# SL_LCD_SW_LED_2E.net
KiCad netlist of a schematic drawn in Altium Designer
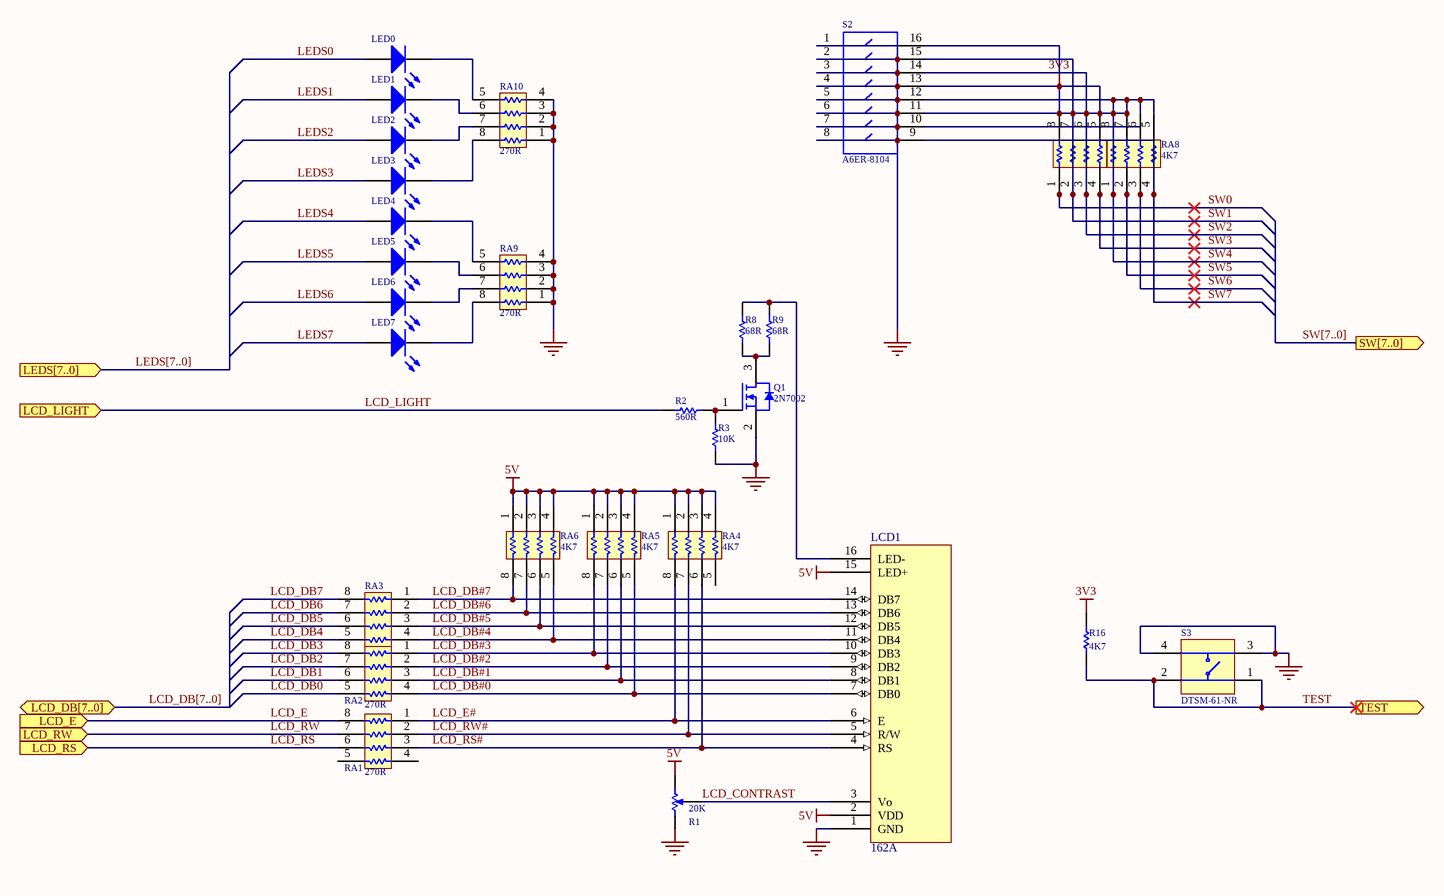
[diagram p0: SL_LCD_SW_LED_2E.SchDoc]

(export (version "E")
  (design (tool "Eeschema 10.0.6"))
  (components
    (comp (ref "LCD1")
      (value "162A")
      (footprint "Spirit_Level_Project:162A")
      (description "16 char * 2 line LCD character display with b/light")
      (libsource (lib "SpiritLevel_2E") (part "162A"))
    )
    (comp (ref "LED0")
      (value "HSMH-C170")
      (footprint "Spirit_Level_Project:SMD _LED")
      (description "Typical RED GaAs SMD LED Agilent make")
      (libsource (lib "SpiritLevel_2E") (part "HSMX-C670"))
    )
    (comp (ref "LED1")
      (value "HSMH-C170")
      (footprint "Spirit_Level_Project:SMD _LED")
      (description "Typical RED GaAs SMD LED Agilent make")
      (libsource (lib "SpiritLevel_2E") (part "HSMX-C670"))
    )
    (comp (ref "LED2")
      (value "HSMH-C170")
      (footprint "Spirit_Level_Project:SMD _LED")
      (description "Typical RED GaAs SMD LED Agilent make")
      (libsource (lib "SpiritLevel_2E") (part "HSMX-C670"))
    )
    (comp (ref "LED3")
      (value "HSMH-C170")
      (footprint "Spirit_Level_Project:SMD _LED")
      (description "Typical RED GaAs SMD LED Agilent make")
      (libsource (lib "SpiritLevel_2E") (part "HSMX-C670"))
    )
    (comp (ref "LED4")
      (value "HSMH-C170")
      (footprint "Spirit_Level_Project:SMD _LED")
      (description "Typical RED GaAs SMD LED Agilent make")
      (libsource (lib "SpiritLevel_2E") (part "HSMX-C670"))
    )
    (comp (ref "LED5")
      (value "HSMH-C170")
      (footprint "Spirit_Level_Project:SMD _LED")
      (description "Typical RED GaAs SMD LED Agilent make")
      (libsource (lib "SpiritLevel_2E") (part "HSMX-C670"))
    )
    (comp (ref "LED6")
      (value "HSMH-C170")
      (footprint "Spirit_Level_Project:SMD _LED")
      (description "Typical RED GaAs SMD LED Agilent make")
      (libsource (lib "SpiritLevel_2E") (part "HSMX-C670"))
    )
    (comp (ref "LED7")
      (value "HSMH-C170")
      (footprint "Spirit_Level_Project:SMD _LED")
      (description "Typical RED GaAs SMD LED Agilent make")
      (libsource (lib "SpiritLevel_2E") (part "HSMX-C670"))
    )
    (comp (ref "Q1")
      (value "2N7002")
      (footprint "Spirit_Level_Project:SO-G3")
      (description "N Channel Mosfet")
      (libsource (lib "SpiritLevel_2E") (part "2N7002"))
    )
    (comp (ref "R1")
      (value "20K")
      (footprint "Spirit_Level_Project:POT4MM-2")
      (description "Square Trimming Potentiometer")
      (libsource (lib "SpiritLevel_2E") (part "RPot SM"))
    )
    (comp (ref "R2")
      (value "560R")
      (footprint "CC2012-0805")
      (description "Resistor")
      (libsource (lib "SpiritLevel_2E") (part "RES"))
    )
    (comp (ref "R3")
      (value "10K")
      (footprint "CC2012-0805")
      (description "Resistor")
      (libsource (lib "SpiritLevel_2E") (part "RES"))
    )
    (comp (ref "R8")
      (value "68R")
      (footprint "CC2012-0805")
      (description "Resistor")
      (libsource (lib "") (part "RES_1"))
    )
    (comp (ref "R9")
      (value "68R")
      (footprint "CC2012-0805")
      (description "Resistor")
      (libsource (lib "") (part "RES_1"))
    )
    (comp (ref "R16")
      (value "4K7")
      (footprint "CC2012-0805")
      (description "Resistor")
      (libsource (lib "SpiritLevel_2E") (part "RES"))
    )
    (comp (ref "RA1")
      (value "270R")
      (footprint "Spirit_Level_Project:MNR34")
      (description "3216x4 Resistor Array")
      (libsource (lib "SpiritLevel_2E") (part "MNR34"))
    )
    (comp (ref "RA2")
      (value "270R")
      (footprint "Spirit_Level_Project:MNR34")
      (description "3216x4 Resistor Array")
      (libsource (lib "SpiritLevel_2E") (part "MNR34"))
    )
    (comp (ref "RA3")
      (value "270R")
      (footprint "Spirit_Level_Project:MNR34")
      (description "3216x4 Resistor Array")
      (libsource (lib "SpiritLevel_2E") (part "MNR34"))
    )
    (comp (ref "RA4")
      (value "4K7")
      (footprint "Spirit_Level_Project:MNR34T")
      (description "3216x4 Resistor Array")
      (libsource (lib "") (part "MNR34_1"))
    )
    (comp (ref "RA5")
      (value "4K7")
      (footprint "Spirit_Level_Project:MNR34T")
      (description "3216x4 Resistor Array")
      (libsource (lib "") (part "MNR34_1"))
    )
    (comp (ref "RA6")
      (value "4K7")
      (footprint "Spirit_Level_Project:MNR34T")
      (description "3216x4 Resistor Array")
      (libsource (lib "") (part "MNR34_1"))
    )
    (comp (ref "RA7")
      (value "4K7")
      (footprint "Spirit_Level_Project:MNR34T")
      (description "3216x4 Resistor Array")
      (libsource (lib "") (part "MNR34_3"))
    )
    (comp (ref "RA8")
      (value "4K7")
      (footprint "Spirit_Level_Project:MNR34T")
      (description "3216x4 Resistor Array")
      (libsource (lib "") (part "MNR34_3"))
    )
    (comp (ref "RA9")
      (value "270R")
      (footprint "Spirit_Level_Project:MNR34T")
      (description "3216x4 Resistor Array")
      (libsource (lib "") (part "MNR34_2"))
    )
    (comp (ref "RA10")
      (value "270R")
      (footprint "Spirit_Level_Project:MNR34T")
      (description "3216x4 Resistor Array")
      (libsource (lib "") (part "MNR34_2"))
    )
    (comp (ref "S2")
      (value "A6ER-8104")
      (footprint "Spirit_Level_Project:DIP-16-KEY")
      (description "DIP Switch Side actuator long liver Piano Key")
      (libsource (lib "SpiritLevel_2E") (part "A6ER-8104"))
    )
    (comp (ref "S3")
      (value "DTSM-61-NR")
      (footprint "Spirit_Level_Project:B3FS_SWITCH")
      (description "SPNA SMD Keyboard Switch")
      (libsource (lib "SpiritLevel_2E") (part "B3FS"))
    )
  )
  (nets
    (net (code "1") (name "/LCD_CONTRAST") (class "Default")
      (node (ref "LCD1") (pin "3") (pinfunction "Vo_3") (pintype "tri_state"))
      (node (ref "R1") (pin "W") (pintype "passive"))
    )
    (net (code "2") (name "/LCD_DB#0") (class "Default")
      (node (ref "LCD1") (pin "7") (pinfunction "DB0_7") (pintype "bidirectional"))
      (node (ref "RA2") (pin "4") (pintype "passive"))
      (node (ref "RA5") (pin "5") (pintype "passive"))
    )
    (net (code "3") (name "/LCD_DB#1") (class "Default")
      (node (ref "LCD1") (pin "8") (pinfunction "DB1_8") (pintype "bidirectional"))
      (node (ref "RA2") (pin "3") (pintype "passive"))
      (node (ref "RA5") (pin "6") (pintype "passive"))
    )
    (net (code "4") (name "/LCD_DB#2") (class "Default")
      (node (ref "LCD1") (pin "9") (pinfunction "DB2_9") (pintype "bidirectional"))
      (node (ref "RA2") (pin "2") (pintype "passive"))
      (node (ref "RA5") (pin "7") (pintype "passive"))
    )
    (net (code "5") (name "/LCD_DB#3") (class "Default")
      (node (ref "LCD1") (pin "10") (pinfunction "DB3_10") (pintype "bidirectional"))
      (node (ref "RA2") (pin "1") (pintype "passive"))
      (node (ref "RA5") (pin "8") (pintype "passive"))
    )
    (net (code "6") (name "/LCD_DB#4") (class "Default")
      (node (ref "LCD1") (pin "11") (pinfunction "DB4_11") (pintype "bidirectional"))
      (node (ref "RA3") (pin "4") (pintype "passive"))
      (node (ref "RA6") (pin "5") (pintype "passive"))
    )
    (net (code "7") (name "/LCD_DB#5") (class "Default")
      (node (ref "LCD1") (pin "12") (pinfunction "DB5_12") (pintype "bidirectional"))
      (node (ref "RA3") (pin "3") (pintype "passive"))
      (node (ref "RA6") (pin "6") (pintype "passive"))
    )
    (net (code "8") (name "/LCD_DB#6") (class "Default")
      (node (ref "LCD1") (pin "13") (pinfunction "DB6_13") (pintype "bidirectional"))
      (node (ref "RA3") (pin "2") (pintype "passive"))
      (node (ref "RA6") (pin "7") (pintype "passive"))
    )
    (net (code "9") (name "/LCD_DB#7") (class "Default")
      (node (ref "LCD1") (pin "14") (pinfunction "DB7_14") (pintype "bidirectional"))
      (node (ref "RA3") (pin "1") (pintype "passive"))
      (node (ref "RA6") (pin "8") (pintype "passive"))
    )
    (net (code "10") (name "/LCD_DB0") (class "Default") (node (ref "RA2") (pin "5") (pintype "passive")))
    (net (code "11") (name "/LCD_DB1") (class "Default") (node (ref "RA2") (pin "6") (pintype "passive")))
    (net (code "12") (name "/LCD_DB2") (class "Default") (node (ref "RA2") (pin "7") (pintype "passive")))
    (net (code "13") (name "/LCD_DB3") (class "Default") (node (ref "RA2") (pin "8") (pintype "passive")))
    (net (code "14") (name "/LCD_DB4") (class "Default") (node (ref "RA3") (pin "5") (pintype "passive")))
    (net (code "15") (name "/LCD_DB5") (class "Default") (node (ref "RA3") (pin "6") (pintype "passive")))
    (net (code "16") (name "/LCD_DB6") (class "Default") (node (ref "RA3") (pin "7") (pintype "passive")))
    (net (code "17") (name "/LCD_DB7") (class "Default") (node (ref "RA3") (pin "8") (pintype "passive")))
    (net (code "19") (name "/LCD_E") (class "Default") (node (ref "RA1") (pin "8") (pintype "passive")))
    (net (code "20") (name "/LCD_E#") (class "Default")
      (node (ref "LCD1") (pin "6") (pinfunction "E_6") (pintype "input"))
      (node (ref "RA1") (pin "1") (pintype "passive"))
      (node (ref "RA4") (pin "8") (pintype "passive"))
    )
    (net (code "21") (name "/LCD_LIGHT") (class "Default")
      (node (ref "R2") (pin "1") (pinfunction "1_1") (pintype "passive"))
    )
    (net (code "22") (name "/LCD_RS") (class "Default") (node (ref "RA1") (pin "6") (pintype "passive")))
    (net (code "23") (name "/LCD_RS#") (class "Default")
      (node (ref "LCD1") (pin "4") (pinfunction "RS_4") (pintype "input"))
      (node (ref "RA1") (pin "3") (pintype "passive"))
      (node (ref "RA4") (pin "6") (pintype "passive"))
    )
    (net (code "24") (name "/LCD_RW") (class "Default") (node (ref "RA1") (pin "7") (pintype "passive")))
    (net (code "25") (name "/LCD_RW#") (class "Default")
      (node (ref "LCD1") (pin "5") (pinfunction "R/W_5") (pintype "input"))
      (node (ref "RA1") (pin "2") (pintype "passive"))
      (node (ref "RA4") (pin "7") (pintype "passive"))
    )
    (net (code "26") (name "/LEDS0") (class "Default")
      (node (ref "LED0") (pin "1") (pinfunction "A_1") (pintype "passive"))
    )
    (net (code "27") (name "/LEDS1") (class "Default")
      (node (ref "LED1") (pin "1") (pinfunction "A_1") (pintype "passive"))
    )
    (net (code "28") (name "/LEDS2") (class "Default")
      (node (ref "LED2") (pin "1") (pinfunction "A_1") (pintype "passive"))
    )
    (net (code "29") (name "/LEDS3") (class "Default")
      (node (ref "LED3") (pin "1") (pinfunction "A_1") (pintype "passive"))
    )
    (net (code "30") (name "/LEDS4") (class "Default")
      (node (ref "LED4") (pin "1") (pinfunction "A_1") (pintype "passive"))
    )
    (net (code "31") (name "/LEDS5") (class "Default")
      (node (ref "LED5") (pin "1") (pinfunction "A_1") (pintype "passive"))
    )
    (net (code "32") (name "/LEDS6") (class "Default")
      (node (ref "LED6") (pin "1") (pinfunction "A_1") (pintype "passive"))
    )
    (net (code "33") (name "/LEDS7") (class "Default")
      (node (ref "LED7") (pin "1") (pinfunction "A_1") (pintype "passive"))
    )
    (net (code "35") (name "/SW6") (class "Default")
      (node (ref "RA8") (pin "3") (pintype "passive"))
      (node (ref "S2") (pin "10") (pinfunction "10_10") (pintype "passive"))
    )
    (net (code "36") (name "/SW7") (class "Default")
      (node (ref "RA8") (pin "4") (pintype "passive"))
      (node (ref "S2") (pin "9") (pinfunction "9_9") (pintype "passive"))
    )
    (net (code "38") (name "/TEST") (class "Default")
      (node (ref "R16") (pin "2") (pinfunction "2_2") (pintype "passive"))
      (node (ref "S3") (pin "1") (pinfunction "1_1") (pintype "passive"))
      (node (ref "S3") (pin "2") (pinfunction "2_2") (pintype "passive"))
    )
    (net (code "39") (name "3V3") (class "Default")
      (node (ref "R16") (pin "1") (pinfunction "1_1") (pintype "passive"))
      (node (ref "RA7") (pin "1") (pintype "passive"))
      (node (ref "RA7") (pin "2") (pintype "passive"))
      (node (ref "RA7") (pin "3") (pintype "passive"))
      (node (ref "RA7") (pin "4") (pintype "passive"))
      (node (ref "RA7") (pin "5") (pintype "passive"))
      (node (ref "RA7") (pin "6") (pintype "passive"))
      (node (ref "RA7") (pin "7") (pintype "passive"))
      (node (ref "RA7") (pin "8") (pintype "passive"))
      (node (ref "RA8") (pin "1") (pintype "passive"))
      (node (ref "RA8") (pin "2") (pintype "passive"))
      (node (ref "RA8") (pin "5") (pintype "passive"))
      (node (ref "RA8") (pin "6") (pintype "passive"))
      (node (ref "RA8") (pin "7") (pintype "passive"))
      (node (ref "RA8") (pin "8") (pintype "passive"))
      (node (ref "S2") (pin "11") (pinfunction "11_11") (pintype "passive"))
      (node (ref "S2") (pin "12") (pinfunction "12_12") (pintype "passive"))
      (node (ref "S2") (pin "13") (pinfunction "13_13") (pintype "passive"))
      (node (ref "S2") (pin "14") (pinfunction "14_14") (pintype "passive"))
      (node (ref "S2") (pin "15") (pinfunction "15_15") (pintype "passive"))
      (node (ref "S2") (pin "16") (pinfunction "16_16") (pintype "passive"))
    )
    (net (code "40") (name "5V") (class "Default")
      (node (ref "LCD1") (pin "15") (pinfunction "LED+_15") (pintype "power_in"))
      (node (ref "LCD1") (pin "2") (pinfunction "VDD_2") (pintype "power_in"))
      (node (ref "R1") (pin "CW") (pinfunction "+_CW") (pintype "passive"))
      (node (ref "RA4") (pin "1") (pintype "passive"))
      (node (ref "RA4") (pin "2") (pintype "passive"))
      (node (ref "RA4") (pin "3") (pintype "passive"))
      (node (ref "RA4") (pin "4") (pintype "passive"))
      (node (ref "RA5") (pin "1") (pintype "passive"))
      (node (ref "RA5") (pin "2") (pintype "passive"))
      (node (ref "RA5") (pin "3") (pintype "passive"))
      (node (ref "RA5") (pin "4") (pintype "passive"))
      (node (ref "RA6") (pin "1") (pintype "passive"))
      (node (ref "RA6") (pin "2") (pintype "passive"))
      (node (ref "RA6") (pin "3") (pintype "passive"))
      (node (ref "RA6") (pin "4") (pintype "passive"))
    )
    (net (code "41") (name "GND") (class "Default")
      (node (ref "LCD1") (pin "1") (pinfunction "GND_1") (pintype "power_in"))
      (node (ref "Q1") (pin "2") (pintype "passive"))
      (node (ref "R1") (pin "CCW") (pinfunction "-_CCW") (pintype "passive"))
      (node (ref "R3") (pin "1") (pinfunction "1_1") (pintype "passive"))
      (node (ref "RA10") (pin "1") (pintype "passive"))
      (node (ref "RA10") (pin "2") (pintype "passive"))
      (node (ref "RA10") (pin "3") (pintype "passive"))
      (node (ref "RA10") (pin "4") (pintype "passive"))
      (node (ref "RA9") (pin "1") (pintype "passive"))
      (node (ref "RA9") (pin "2") (pintype "passive"))
      (node (ref "RA9") (pin "3") (pintype "passive"))
      (node (ref "RA9") (pin "4") (pintype "passive"))
      (node (ref "S2") (pin "1") (pinfunction "1_1") (pintype "passive"))
      (node (ref "S2") (pin "2") (pinfunction "2_2") (pintype "passive"))
      (node (ref "S2") (pin "3") (pinfunction "3_3") (pintype "passive"))
      (node (ref "S2") (pin "4") (pinfunction "4_4") (pintype "passive"))
      (node (ref "S2") (pin "5") (pinfunction "5_5") (pintype "passive"))
      (node (ref "S2") (pin "6") (pinfunction "6_6") (pintype "passive"))
      (node (ref "S2") (pin "7") (pinfunction "7_7") (pintype "passive"))
      (node (ref "S2") (pin "8") (pinfunction "8_8") (pintype "passive"))
      (node (ref "S3") (pin "3") (pinfunction "3_3") (pintype "passive"))
      (node (ref "S3") (pin "4") (pinfunction "4_4") (pintype "passive"))
    )
    (net (code "42") (name "Net-(LCD1-LED-)") (class "Default")
      (node (ref "LCD1") (pin "16") (pinfunction "LED-_16") (pintype "power_in"))
      (node (ref "R8") (pin "1") (pinfunction "1_1") (pintype "passive"))
      (node (ref "R9") (pin "1") (pinfunction "1_1") (pintype "passive"))
    )
    (net (code "43") (name "Net-(LED0-K)") (class "Default")
      (node (ref "LED0") (pin "2") (pinfunction "K_2") (pintype "passive"))
      (node (ref "RA10") (pin "5") (pintype "passive"))
    )
    (net (code "44") (name "Net-(LED1-K)") (class "Default")
      (node (ref "LED1") (pin "2") (pinfunction "K_2") (pintype "passive"))
      (node (ref "RA10") (pin "6") (pintype "passive"))
    )
    (net (code "45") (name "Net-(LED2-K)") (class "Default")
      (node (ref "LED2") (pin "2") (pinfunction "K_2") (pintype "passive"))
      (node (ref "RA10") (pin "7") (pintype "passive"))
    )
    (net (code "46") (name "Net-(LED3-K)") (class "Default")
      (node (ref "LED3") (pin "2") (pinfunction "K_2") (pintype "passive"))
      (node (ref "RA10") (pin "8") (pintype "passive"))
    )
    (net (code "47") (name "Net-(LED4-K)") (class "Default")
      (node (ref "LED4") (pin "2") (pinfunction "K_2") (pintype "passive"))
      (node (ref "RA9") (pin "5") (pintype "passive"))
    )
    (net (code "48") (name "Net-(LED5-K)") (class "Default")
      (node (ref "LED5") (pin "2") (pinfunction "K_2") (pintype "passive"))
      (node (ref "RA9") (pin "6") (pintype "passive"))
    )
    (net (code "49") (name "Net-(LED6-K)") (class "Default")
      (node (ref "LED6") (pin "2") (pinfunction "K_2") (pintype "passive"))
      (node (ref "RA9") (pin "7") (pintype "passive"))
    )
    (net (code "50") (name "Net-(LED7-K)") (class "Default")
      (node (ref "LED7") (pin "2") (pinfunction "K_2") (pintype "passive"))
      (node (ref "RA9") (pin "8") (pintype "passive"))
    )
    (net (code "51") (name "Net-(Q1-Pad1)") (class "Default")
      (node (ref "Q1") (pin "1") (pintype "passive"))
      (node (ref "R2") (pin "2") (pinfunction "2_2") (pintype "passive"))
      (node (ref "R3") (pin "2") (pinfunction "2_2") (pintype "passive"))
    )
    (net (code "52") (name "Net-(Q1-Pad3)") (class "Default")
      (node (ref "Q1") (pin "3") (pintype "passive"))
      (node (ref "R8") (pin "2") (pinfunction "2_2") (pintype "passive"))
      (node (ref "R9") (pin "2") (pinfunction "2_2") (pintype "passive"))
    )
    (net (code "53") (name "unconnected-(RA1-Pad4)") (class "Default")
      (node (ref "RA1") (pin "4") (pintype "passive"))
    )
    (net (code "54") (name "unconnected-(RA1-Pad5)") (class "Default")
      (node (ref "RA1") (pin "5") (pintype "passive"))
    )
    (net (code "55") (name "unconnected-(RA4-Pad5)") (class "Default")
      (node (ref "RA4") (pin "5") (pintype "passive"))
    )
  )
)
